# lcd13264-module-example.net
KiCad netlist of a schematic drawn in EAGLE
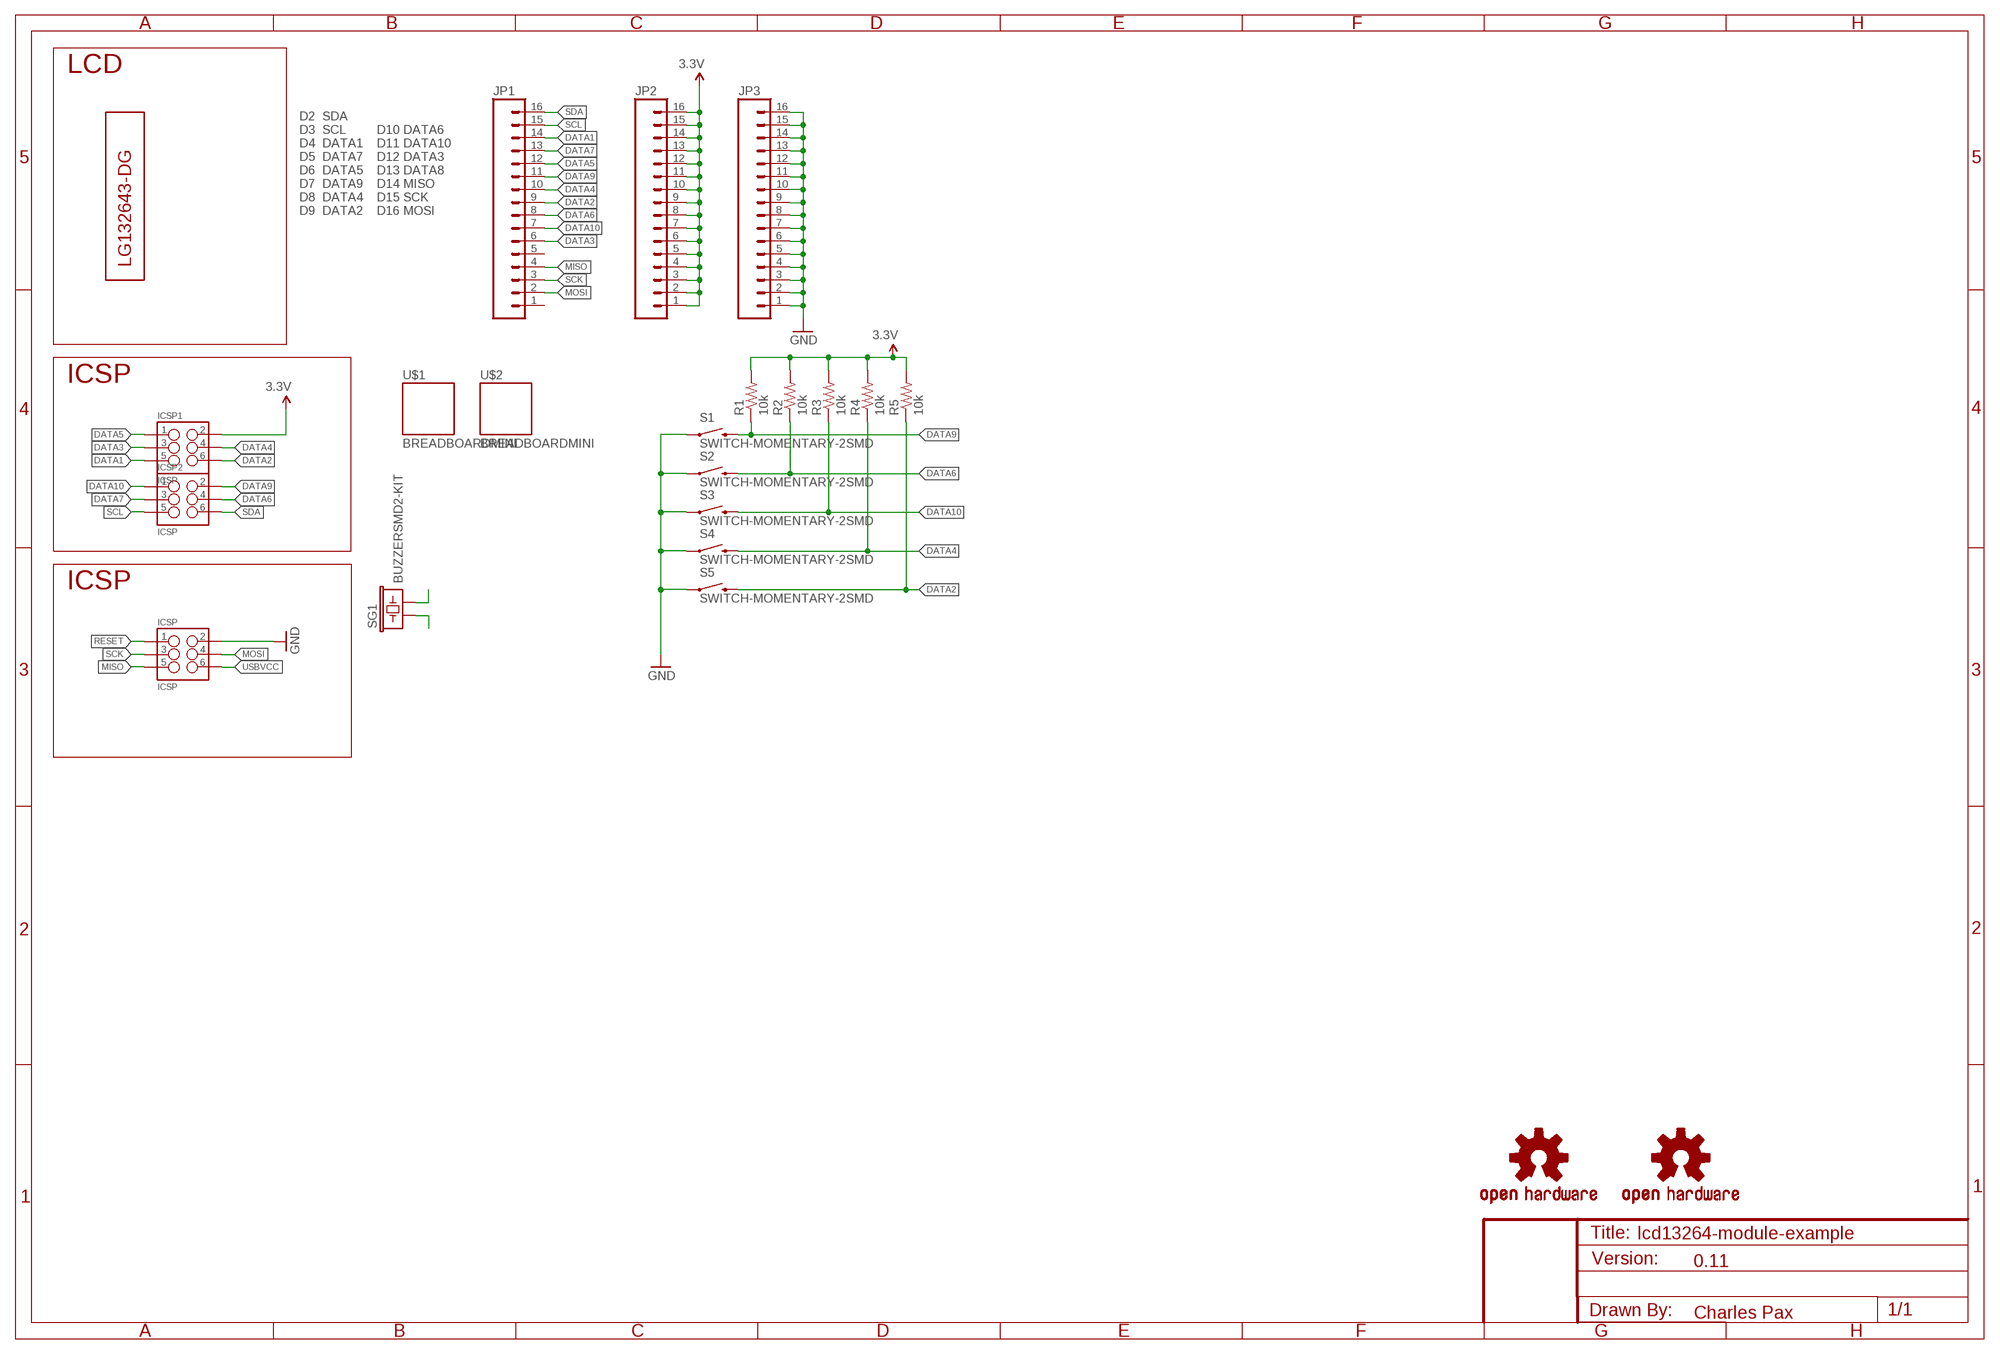
[diagram p0: schematic, sheet 1]

(export (version "E")
  (design (tool "Eeschema 10.0.6"))
  (components
    (comp (ref "ICSP")
      (value "ICSP")
      (footprint "eagle-import:SPARKFUN-CONNECTORS_2X3_SMT_POSTS_PAXINSTRUMENT")
      (fields (field (name "MPN") "95278-101A06LF"))
      (libsource (lib "eagle-import") (part "SPARKFUN-CONNECTORS_M03X2PAX"))
    )
    (comp (ref "ICSP1")
      (value "ICSP")
      (footprint "eagle-import:SPARKFUN-CONNECTORS_2X3_SMT_POSTS_PAXINSTRUMENT")
      (fields (field (name "MPN") "95278-101A06LF"))
      (libsource (lib "eagle-import") (part "SPARKFUN-CONNECTORS_M03X2PAX"))
    )
    (comp (ref "ICSP2")
      (value "ICSP")
      (footprint "eagle-import:SPARKFUN-CONNECTORS_2X3_SMT_POSTS_PAXINSTRUMENT")
      (fields (field (name "MPN") "95278-101A06LF"))
      (libsource (lib "eagle-import") (part "SPARKFUN-CONNECTORS_M03X2PAX"))
    )
    (comp (ref "JP1")
      (value "M161X16_NO_SILK")
      (footprint "eagle-import:1X16_NO_SILK")
      (libsource (lib "eagle-import") (part "M161X16_NO_SILK"))
    )
    (comp (ref "JP2")
      (value "M161X16_NO_SILK")
      (footprint "eagle-import:1X16_NO_SILK")
      (libsource (lib "eagle-import") (part "M161X16_NO_SILK"))
    )
    (comp (ref "JP3")
      (value "M161X16_NO_SILK")
      (footprint "eagle-import:1X16_NO_SILK")
      (libsource (lib "eagle-import") (part "M161X16_NO_SILK"))
    )
    (comp (ref "LOGO1")
      (value "OSHW-LOGOL")
      (footprint "eagle-import:OSHW-LOGO-L")
      (libsource (lib "eagle-import") (part "OSHW-LOGOL"))
    )
    (comp (ref "LOGO2")
      (value "OSHW-LOGOL-COPPER")
      (footprint "eagle-import:OSHW-LOGO-L_COPPER")
      (libsource (lib "eagle-import") (part "OSHW-LOGOL-COPPER"))
    )
    (comp (ref "R1")
      (value "10k")
      (footprint "eagle-import:0603-RES")
      (libsource (lib "eagle-import") (part "RESISTOR0603-RES"))
    )
    (comp (ref "R2")
      (value "10k")
      (footprint "eagle-import:0603-RES")
      (libsource (lib "eagle-import") (part "RESISTOR0603-RES"))
    )
    (comp (ref "R3")
      (value "10k")
      (footprint "eagle-import:0603-RES")
      (libsource (lib "eagle-import") (part "RESISTOR0603-RES"))
    )
    (comp (ref "R4")
      (value "10k")
      (footprint "eagle-import:0603-RES")
      (libsource (lib "eagle-import") (part "RESISTOR0603-RES"))
    )
    (comp (ref "R5")
      (value "10k")
      (footprint "eagle-import:0603-RES")
      (libsource (lib "eagle-import") (part "RESISTOR0603-RES"))
    )
    (comp (ref "S1")
      (value "SWITCH-MOMENTARY-2SMD")
      (footprint "eagle-import:TACTILE-SWITCH-SMD")
      (libsource (lib "eagle-import") (part "SWITCH-MOMENTARY-2SMD"))
    )
    (comp (ref "S2")
      (value "SWITCH-MOMENTARY-2SMD")
      (footprint "eagle-import:TACTILE-SWITCH-SMD")
      (libsource (lib "eagle-import") (part "SWITCH-MOMENTARY-2SMD"))
    )
    (comp (ref "S3")
      (value "SWITCH-MOMENTARY-2SMD")
      (footprint "eagle-import:TACTILE-SWITCH-SMD")
      (libsource (lib "eagle-import") (part "SWITCH-MOMENTARY-2SMD"))
    )
    (comp (ref "S4")
      (value "SWITCH-MOMENTARY-2SMD")
      (footprint "eagle-import:TACTILE-SWITCH-SMD")
      (libsource (lib "eagle-import") (part "SWITCH-MOMENTARY-2SMD"))
    )
    (comp (ref "S5")
      (value "SWITCH-MOMENTARY-2SMD")
      (footprint "eagle-import:TACTILE-SWITCH-SMD")
      (libsource (lib "eagle-import") (part "SWITCH-MOMENTARY-2SMD"))
    )
    (comp (ref "SG1")
      (value "BUZZERSMD2-KIT")
      (footprint "eagle-import:BUZZER-CCV-KIT")
      (libsource (lib "eagle-import") (part "BUZZERSMD2-KIT"))
    )
    (comp (ref "U$1")
      (value "BREADBOARDMINI")
      (footprint "eagle-import:BREADBOARD-MINI")
      (libsource (lib "eagle-import") (part "BREADBOARDMINI"))
    )
    (comp (ref "U$2")
      (value "BREADBOARDMINI")
      (footprint "eagle-import:BREADBOARD-MINI")
      (libsource (lib "eagle-import") (part "BREADBOARDMINI"))
    )
    (comp (ref "U$5")
      (value "LG132643-DG")
      (footprint "eagle-import:LG132643-DG")
      (fields (field (name "MPN") "LG132643-DW"))
      (libsource (lib "eagle-import") (part "LG132643-DG"))
    )
  )
  (nets
    (net (code "1") (name "3.3V") (class "Default")
      (node (ref "ICSP1") (pin "2") (pinfunction "2_2") (pintype "bidirectional"))
      (node (ref "JP2") (pin "1") (pinfunction "1_1") (pintype "passive"))
      (node (ref "JP2") (pin "10") (pinfunction "10_10") (pintype "passive"))
      (node (ref "JP2") (pin "11") (pinfunction "11_11") (pintype "passive"))
      (node (ref "JP2") (pin "12") (pinfunction "12_12") (pintype "passive"))
      (node (ref "JP2") (pin "13") (pinfunction "13_13") (pintype "passive"))
      (node (ref "JP2") (pin "14") (pinfunction "14_14") (pintype "passive"))
      (node (ref "JP2") (pin "15") (pinfunction "15_15") (pintype "passive"))
      (node (ref "JP2") (pin "16") (pinfunction "16_16") (pintype "passive"))
      (node (ref "JP2") (pin "2") (pinfunction "2_2") (pintype "passive"))
      (node (ref "JP2") (pin "3") (pinfunction "3_3") (pintype "passive"))
      (node (ref "JP2") (pin "4") (pinfunction "4_4") (pintype "passive"))
      (node (ref "JP2") (pin "5") (pinfunction "5_5") (pintype "passive"))
      (node (ref "JP2") (pin "6") (pinfunction "6_6") (pintype "passive"))
      (node (ref "JP2") (pin "7") (pinfunction "7_7") (pintype "passive"))
      (node (ref "JP2") (pin "8") (pinfunction "8_8") (pintype "passive"))
      (node (ref "JP2") (pin "9") (pinfunction "9_9") (pintype "passive"))
      (node (ref "R1") (pin "2") (pinfunction "2_2") (pintype "passive"))
      (node (ref "R2") (pin "2") (pinfunction "2_2") (pintype "passive"))
      (node (ref "R3") (pin "2") (pinfunction "2_2") (pintype "passive"))
      (node (ref "R4") (pin "2") (pinfunction "2_2") (pintype "passive"))
      (node (ref "R5") (pin "2") (pinfunction "2_2") (pintype "passive"))
    )
    (net (code "2") (name "DATA1") (class "Default")
      (node (ref "ICSP1") (pin "5") (pinfunction "5_5") (pintype "bidirectional"))
      (node (ref "JP1") (pin "14") (pinfunction "14_14") (pintype "passive"))
    )
    (net (code "3") (name "DATA2") (class "Default")
      (node (ref "ICSP1") (pin "6") (pinfunction "6_6") (pintype "bidirectional"))
      (node (ref "JP1") (pin "9") (pinfunction "9_9") (pintype "passive"))
      (node (ref "R5") (pin "1") (pinfunction "1_1") (pintype "passive"))
      (node (ref "S5") (pin "3") (pinfunction "2_3") (pintype "passive"))
    )
    (net (code "4") (name "DATA3") (class "Default")
      (node (ref "ICSP1") (pin "3") (pinfunction "3_3") (pintype "bidirectional"))
      (node (ref "JP1") (pin "6") (pinfunction "6_6") (pintype "passive"))
    )
    (net (code "5") (name "DATA4") (class "Default")
      (node (ref "ICSP1") (pin "4") (pinfunction "4_4") (pintype "bidirectional"))
      (node (ref "JP1") (pin "10") (pinfunction "10_10") (pintype "passive"))
      (node (ref "R4") (pin "1") (pinfunction "1_1") (pintype "passive"))
      (node (ref "S4") (pin "3") (pinfunction "2_3") (pintype "passive"))
    )
    (net (code "6") (name "DATA5") (class "Default")
      (node (ref "ICSP1") (pin "1") (pinfunction "1_1") (pintype "bidirectional"))
      (node (ref "JP1") (pin "12") (pinfunction "12_12") (pintype "passive"))
    )
    (net (code "7") (name "DATA6") (class "Default")
      (node (ref "ICSP2") (pin "4") (pinfunction "4_4") (pintype "bidirectional"))
      (node (ref "JP1") (pin "8") (pinfunction "8_8") (pintype "passive"))
      (node (ref "R2") (pin "1") (pinfunction "1_1") (pintype "passive"))
      (node (ref "S2") (pin "3") (pinfunction "2_3") (pintype "passive"))
    )
    (net (code "8") (name "DATA7") (class "Default")
      (node (ref "ICSP2") (pin "3") (pinfunction "3_3") (pintype "bidirectional"))
      (node (ref "JP1") (pin "13") (pinfunction "13_13") (pintype "passive"))
    )
    (net (code "9") (name "DATA9") (class "Default")
      (node (ref "ICSP2") (pin "2") (pinfunction "2_2") (pintype "bidirectional"))
      (node (ref "JP1") (pin "11") (pinfunction "11_11") (pintype "passive"))
      (node (ref "R1") (pin "1") (pinfunction "1_1") (pintype "passive"))
      (node (ref "S1") (pin "3") (pinfunction "2_3") (pintype "passive"))
    )
    (net (code "10") (name "DATA10") (class "Default")
      (node (ref "ICSP2") (pin "1") (pinfunction "1_1") (pintype "bidirectional"))
      (node (ref "JP1") (pin "7") (pinfunction "7_7") (pintype "passive"))
      (node (ref "R3") (pin "1") (pinfunction "1_1") (pintype "passive"))
      (node (ref "S3") (pin "3") (pinfunction "2_3") (pintype "passive"))
    )
    (net (code "11") (name "GND") (class "Default")
      (node (ref "ICSP") (pin "2") (pinfunction "2_2") (pintype "bidirectional"))
      (node (ref "JP3") (pin "1") (pinfunction "1_1") (pintype "passive"))
      (node (ref "JP3") (pin "10") (pinfunction "10_10") (pintype "passive"))
      (node (ref "JP3") (pin "11") (pinfunction "11_11") (pintype "passive"))
      (node (ref "JP3") (pin "12") (pinfunction "12_12") (pintype "passive"))
      (node (ref "JP3") (pin "13") (pinfunction "13_13") (pintype "passive"))
      (node (ref "JP3") (pin "14") (pinfunction "14_14") (pintype "passive"))
      (node (ref "JP3") (pin "15") (pinfunction "15_15") (pintype "passive"))
      (node (ref "JP3") (pin "16") (pinfunction "16_16") (pintype "passive"))
      (node (ref "JP3") (pin "2") (pinfunction "2_2") (pintype "passive"))
      (node (ref "JP3") (pin "3") (pinfunction "3_3") (pintype "passive"))
      (node (ref "JP3") (pin "4") (pinfunction "4_4") (pintype "passive"))
      (node (ref "JP3") (pin "5") (pinfunction "5_5") (pintype "passive"))
      (node (ref "JP3") (pin "6") (pinfunction "6_6") (pintype "passive"))
      (node (ref "JP3") (pin "7") (pinfunction "7_7") (pintype "passive"))
      (node (ref "JP3") (pin "8") (pinfunction "8_8") (pintype "passive"))
      (node (ref "JP3") (pin "9") (pinfunction "9_9") (pintype "passive"))
      (node (ref "S1") (pin "1") (pinfunction "1_1") (pintype "passive"))
      (node (ref "S2") (pin "1") (pinfunction "1_1") (pintype "passive"))
      (node (ref "S3") (pin "1") (pinfunction "1_1") (pintype "passive"))
      (node (ref "S4") (pin "1") (pinfunction "1_1") (pintype "passive"))
      (node (ref "S5") (pin "1") (pinfunction "1_1") (pintype "passive"))
    )
    (net (code "12") (name "MISO") (class "Default")
      (node (ref "ICSP") (pin "5") (pinfunction "5_5") (pintype "bidirectional"))
      (node (ref "JP1") (pin "4") (pinfunction "4_4") (pintype "passive"))
    )
    (net (code "13") (name "MOSI") (class "Default")
      (node (ref "ICSP") (pin "4") (pinfunction "4_4") (pintype "bidirectional"))
      (node (ref "JP1") (pin "2") (pinfunction "2_2") (pintype "passive"))
    )
    (net (code "14") (name "RESET") (class "Default")
      (node (ref "ICSP") (pin "1") (pinfunction "1_1") (pintype "bidirectional"))
    )
    (net (code "15") (name "SCK") (class "Default")
      (node (ref "ICSP") (pin "3") (pinfunction "3_3") (pintype "bidirectional"))
      (node (ref "JP1") (pin "3") (pinfunction "3_3") (pintype "passive"))
    )
    (net (code "16") (name "SCL") (class "Default")
      (node (ref "ICSP2") (pin "5") (pinfunction "5_5") (pintype "bidirectional"))
      (node (ref "JP1") (pin "15") (pinfunction "15_15") (pintype "passive"))
    )
    (net (code "17") (name "SDA") (class "Default")
      (node (ref "ICSP2") (pin "6") (pinfunction "6_6") (pintype "bidirectional"))
      (node (ref "JP1") (pin "16") (pinfunction "16_16") (pintype "passive"))
    )
    (net (code "18") (name "USBVCC") (class "Default")
      (node (ref "ICSP") (pin "6") (pinfunction "6_6") (pintype "bidirectional"))
    )
    (net (code "19") (name "unconnected-(JP1-Pad1)") (class "Default")
      (node (ref "JP1") (pin "1") (pinfunction "1_1") (pintype "passive"))
    )
    (net (code "20") (name "unconnected-(JP1-Pad5)") (class "Default")
      (node (ref "JP1") (pin "5") (pinfunction "5_5") (pintype "passive"))
    )
    (net (code "21") (name "unconnected-(SG1-1-Pad+)") (class "Default")
      (node (ref "SG1") (pin "+") (pinfunction "1_+") (pintype "passive"))
    )
    (net (code "22") (name "unconnected-(SG1-2-Pad-)") (class "Default")
      (node (ref "SG1") (pin "-") (pinfunction "2_-") (pintype "passive"))
    )
  )
)
